# HIP4081A_v1_2.net
KiCad netlist of a schematic drawn in EAGLE
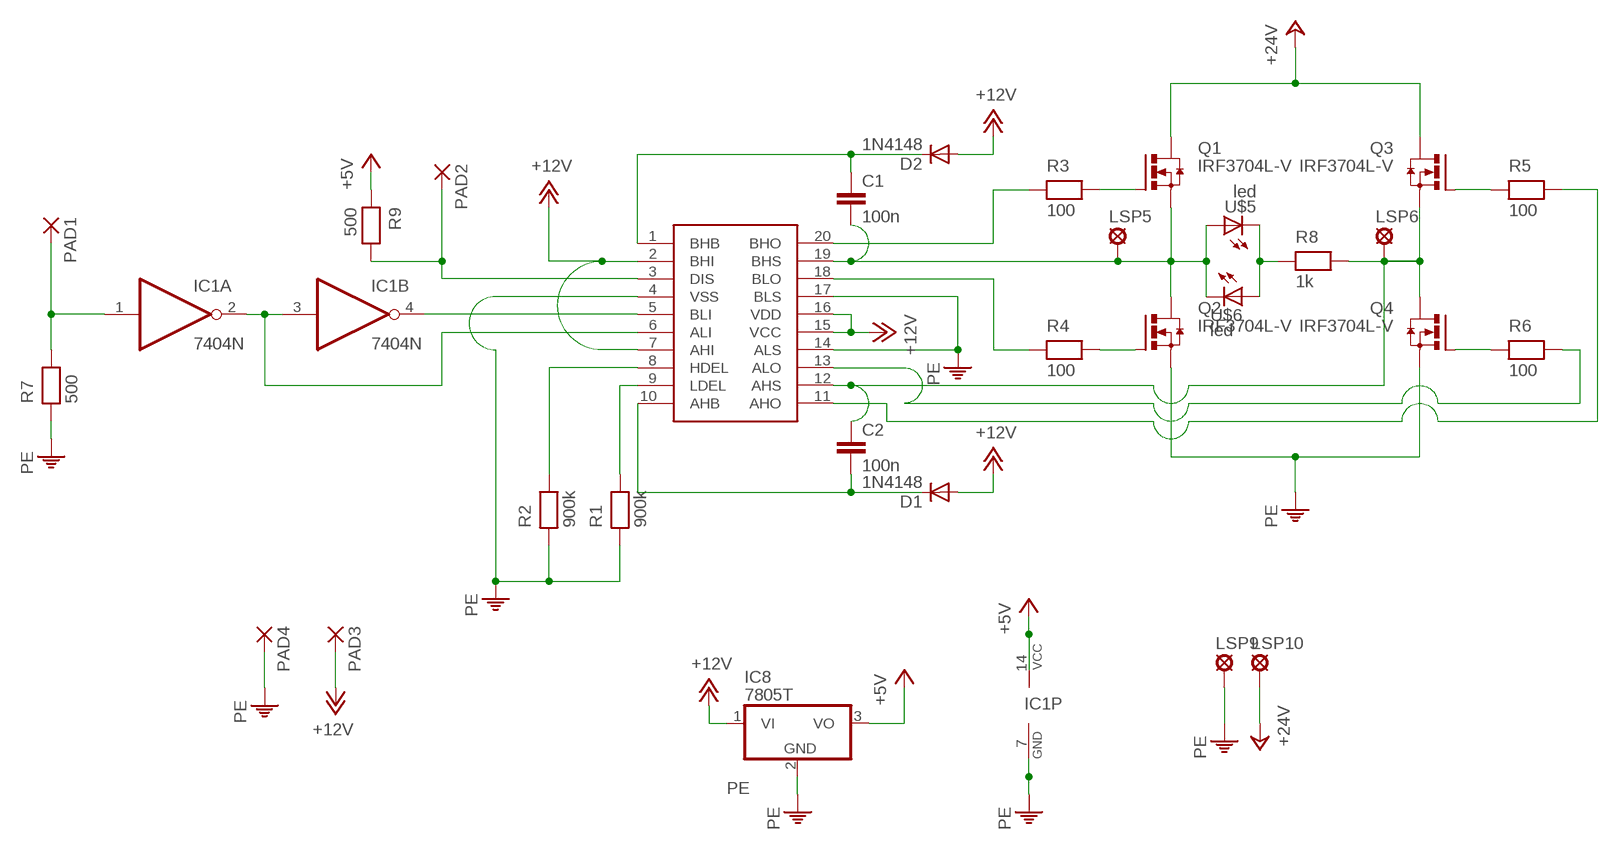
[diagram p0: schematic, sheet 1]

(export (version "E")
  (design (tool "Eeschema 10.0.6"))
  (components
    (comp (ref "C1")
      (value "100n")
      (footprint "eagle-import:C5B2.5")
      (libsource (lib "eagle-import") (part "C5/2.5"))
    )
    (comp (ref "C2")
      (value "100n")
      (footprint "eagle-import:C5B2.5")
      (libsource (lib "eagle-import") (part "C5/2.5"))
    )
    (comp (ref "D1")
      (value "1N4148")
      (footprint "eagle-import:DO35-10")
      (libsource (lib "eagle-import") (part "1N4148"))
    )
    (comp (ref "D2")
      (value "1N4148")
      (footprint "eagle-import:DO35-10")
      (libsource (lib "eagle-import") (part "1N4148"))
    )
    (comp (ref "IC1")
      (value "7404N")
      (footprint "eagle-import:DIL14")
      (libsource (lib "eagle-import") (part "7404N"))
    )
    (comp (ref "IC2")
      (value "HIP4081A")
      (footprint "eagle-import:DIL20")
      (libsource (lib "eagle-import") (part "HIP4081A"))
    )
    (comp (ref "IC8")
      (value "7805T")
      (footprint "eagle-import:TO220H")
      (libsource (lib "eagle-import") (part "78T05"))
    )
    (comp (ref "LSP5")
      (value "SE14")
      (footprint "eagle-import:SE14")
      (libsource (lib "eagle-import") (part "SE14"))
    )
    (comp (ref "LSP6")
      (value "SE14")
      (footprint "eagle-import:SE14")
      (libsource (lib "eagle-import") (part "SE14"))
    )
    (comp (ref "LSP9")
      (value "SE14")
      (footprint "eagle-import:SE14")
      (libsource (lib "eagle-import") (part "SE14"))
    )
    (comp (ref "LSP10")
      (value "SE14")
      (footprint "eagle-import:SE14")
      (libsource (lib "eagle-import") (part "SE14"))
    )
    (comp (ref "PAD1")
      (value "1,6/0,8")
      (footprint "eagle-import:1,6_0,8")
      (libsource (lib "eagle-import") (part "1,6/0,8"))
    )
    (comp (ref "PAD2")
      (value "1,6/0,8")
      (footprint "eagle-import:1,6_0,8")
      (libsource (lib "eagle-import") (part "1,6/0,8"))
    )
    (comp (ref "PAD3")
      (value "1,6/0,8")
      (footprint "eagle-import:1,6_0,8")
      (libsource (lib "eagle-import") (part "1,6/0,8"))
    )
    (comp (ref "PAD4")
      (value "1,6/0,8")
      (footprint "eagle-import:1,6_0,8")
      (libsource (lib "eagle-import") (part "1,6/0,8"))
    )
    (comp (ref "Q1")
      (value "IRF3704L-V")
      (footprint "eagle-import:TO262-V")
      (libsource (lib "eagle-import") (part "IRF3704L-V"))
    )
    (comp (ref "Q2")
      (value "IRF3704L-V")
      (footprint "eagle-import:TO262-V")
      (libsource (lib "eagle-import") (part "IRF3704L-V"))
    )
    (comp (ref "Q3")
      (value "IRF3704L-V")
      (footprint "eagle-import:TO262-V")
      (libsource (lib "eagle-import") (part "IRF3704L-V"))
    )
    (comp (ref "Q4")
      (value "IRF3704L-V")
      (footprint "eagle-import:TO262-V")
      (libsource (lib "eagle-import") (part "IRF3704L-V"))
    )
    (comp (ref "R1")
      (value "900k")
      (footprint "eagle-import:R-10")
      (libsource (lib "eagle-import") (part "RESEU-10"))
    )
    (comp (ref "R2")
      (value "900k")
      (footprint "eagle-import:R-10")
      (libsource (lib "eagle-import") (part "RESEU-10"))
    )
    (comp (ref "R3")
      (value "100")
      (footprint "eagle-import:R-10")
      (libsource (lib "eagle-import") (part "RESEU-10"))
    )
    (comp (ref "R4")
      (value "100")
      (footprint "eagle-import:R-10")
      (libsource (lib "eagle-import") (part "RESEU-10"))
    )
    (comp (ref "R5")
      (value "100")
      (footprint "eagle-import:R-10")
      (libsource (lib "eagle-import") (part "RESEU-10"))
    )
    (comp (ref "R6")
      (value "100")
      (footprint "eagle-import:R-10")
      (libsource (lib "eagle-import") (part "RESEU-10"))
    )
    (comp (ref "R7")
      (value "500")
      (footprint "eagle-import:R-10")
      (libsource (lib "eagle-import") (part "RESEU-10"))
    )
    (comp (ref "R8")
      (value "1k")
      (footprint "eagle-import:R-10")
      (libsource (lib "eagle-import") (part "RESEU-10"))
    )
    (comp (ref "R9")
      (value "500")
      (footprint "eagle-import:R-10")
      (libsource (lib "eagle-import") (part "RESEU-10"))
    )
    (comp (ref "U$5")
      (value "led")
      (footprint "eagle-import:LED3MM")
      (libsource (lib "eagle-import") (part "LED3MM"))
    )
    (comp (ref "U$6")
      (value "led")
      (footprint "eagle-import:LED3MM")
      (libsource (lib "eagle-import") (part "LED3MM"))
    )
  )
  (nets
    (net (code "1") (name "+5V") (class "Default")
      (node (ref "IC1") (pin "14") (pinfunction "VCC_14") (pintype "power_in"))
      (node (ref "IC8") (pin "3") (pinfunction "VO_3") (pintype "passive"))
      (node (ref "R9") (pin "1") (pinfunction "1_1") (pintype "passive"))
    )
    (net (code "2") (name "+12V") (class "Default")
      (node (ref "D1") (pin "A") (pinfunction "A_A") (pintype "passive"))
      (node (ref "D2") (pin "A") (pinfunction "A_A") (pintype "passive"))
      (node (ref "IC2") (pin "15") (pinfunction "VCC_15") (pintype "input"))
      (node (ref "IC2") (pin "16") (pinfunction "VDD_16") (pintype "input"))
      (node (ref "IC2") (pin "2") (pinfunction "BHI_2") (pintype "bidirectional"))
      (node (ref "IC2") (pin "7") (pinfunction "AHI_7") (pintype "bidirectional"))
      (node (ref "IC8") (pin "1") (pinfunction "VI_1") (pintype "input"))
      (node (ref "PAD3") (pin "1") (pinfunction "P_1") (pintype "passive"))
    )
    (net (code "3") (name "+24V") (class "Default")
      (node (ref "LSP10") (pin "MP") (pinfunction "MP_MP") (pintype "passive"))
      (node (ref "Q1") (pin "2") (pinfunction "D_2") (pintype "passive"))
      (node (ref "Q3") (pin "2") (pinfunction "D_2") (pintype "passive"))
    )
    (net (code "4") (name "Net-(IC1A-I)") (class "Default")
      (node (ref "IC1") (pin "1") (pinfunction "I_1") (pintype "input"))
      (node (ref "PAD1") (pin "1") (pinfunction "P_1") (pintype "passive"))
      (node (ref "R7") (pin "2") (pinfunction "2_2") (pintype "passive"))
    )
    (net (code "5") (name "Net-(IC1A-O)") (class "Default")
      (node (ref "IC1") (pin "2") (pinfunction "O_2") (pintype "output"))
      (node (ref "IC1") (pin "3") (pinfunction "I_3") (pintype "input"))
      (node (ref "IC2") (pin "6") (pinfunction "ALI_6") (pintype "bidirectional"))
    )
    (net (code "6") (name "Net-(IC1B-O)") (class "Default")
      (node (ref "IC1") (pin "4") (pinfunction "O_4") (pintype "output"))
      (node (ref "IC2") (pin "5") (pinfunction "BLI_5") (pintype "bidirectional"))
    )
    (net (code "7") (name "Net-(IC2-AHB)") (class "Default")
      (node (ref "C2") (pin "2") (pinfunction "2_2") (pintype "passive"))
      (node (ref "D1") (pin "C") (pinfunction "C_C") (pintype "passive"))
      (node (ref "IC2") (pin "10") (pinfunction "AHB_10") (pintype "bidirectional"))
    )
    (net (code "8") (name "Net-(IC2-AHO)") (class "Default")
      (node (ref "IC2") (pin "11") (pinfunction "AHO_11") (pintype "output"))
      (node (ref "R5") (pin "2") (pinfunction "2_2") (pintype "passive"))
    )
    (net (code "9") (name "Net-(IC2-AHS)") (class "Default")
      (node (ref "C2") (pin "1") (pinfunction "1_1") (pintype "passive"))
      (node (ref "IC2") (pin "12") (pinfunction "AHS_12") (pintype "input"))
      (node (ref "LSP6") (pin "MP") (pinfunction "MP_MP") (pintype "passive"))
      (node (ref "Q3") (pin "3") (pinfunction "S_3") (pintype "passive"))
      (node (ref "Q4") (pin "2") (pinfunction "D_2") (pintype "passive"))
      (node (ref "R8") (pin "2") (pinfunction "2_2") (pintype "passive"))
    )
    (net (code "10") (name "Net-(IC2-ALO)") (class "Default")
      (node (ref "IC2") (pin "13") (pinfunction "ALO_13") (pintype "output"))
      (node (ref "R6") (pin "2") (pinfunction "2_2") (pintype "passive"))
    )
    (net (code "11") (name "Net-(IC2-BHB)") (class "Default")
      (node (ref "C1") (pin "1") (pinfunction "1_1") (pintype "passive"))
      (node (ref "D2") (pin "C") (pinfunction "C_C") (pintype "passive"))
      (node (ref "IC2") (pin "1") (pinfunction "BHB_1") (pintype "bidirectional"))
    )
    (net (code "12") (name "Net-(IC2-BHO)") (class "Default")
      (node (ref "IC2") (pin "20") (pinfunction "BHO_20") (pintype "output"))
      (node (ref "R3") (pin "1") (pinfunction "1_1") (pintype "passive"))
    )
    (net (code "13") (name "Net-(IC2-BHS)") (class "Default")
      (node (ref "C1") (pin "2") (pinfunction "2_2") (pintype "passive"))
      (node (ref "IC2") (pin "19") (pinfunction "BHS_19") (pintype "input"))
      (node (ref "LSP5") (pin "MP") (pinfunction "MP_MP") (pintype "passive"))
      (node (ref "Q1") (pin "3") (pinfunction "S_3") (pintype "passive"))
      (node (ref "Q2") (pin "2") (pinfunction "D_2") (pintype "passive"))
      (node (ref "U$5") (pin "A") (pinfunction "A_A") (pintype "passive"))
      (node (ref "U$6") (pin "K") (pinfunction "C_K") (pintype "passive"))
    )
    (net (code "14") (name "Net-(IC2-BLO)") (class "Default")
      (node (ref "IC2") (pin "18") (pinfunction "BLO_18") (pintype "output"))
      (node (ref "R4") (pin "1") (pinfunction "1_1") (pintype "passive"))
    )
    (net (code "15") (name "Net-(IC2-DIS)") (class "Default")
      (node (ref "IC2") (pin "3") (pinfunction "DIS_3") (pintype "input"))
      (node (ref "PAD2") (pin "1") (pinfunction "P_1") (pintype "passive"))
      (node (ref "R9") (pin "2") (pinfunction "2_2") (pintype "passive"))
    )
    (net (code "16") (name "Net-(IC2-HDEL)") (class "Default")
      (node (ref "IC2") (pin "8") (pinfunction "HDEL_8") (pintype "bidirectional"))
      (node (ref "R2") (pin "2") (pinfunction "2_2") (pintype "passive"))
    )
    (net (code "17") (name "Net-(IC2-LDEL)") (class "Default")
      (node (ref "IC2") (pin "9") (pinfunction "LDEL_9") (pintype "bidirectional"))
      (node (ref "R1") (pin "2") (pinfunction "2_2") (pintype "passive"))
    )
    (net (code "18") (name "Net-(Q1-G)") (class "Default")
      (node (ref "Q1") (pin "1") (pinfunction "G_1") (pintype "passive"))
      (node (ref "R3") (pin "2") (pinfunction "2_2") (pintype "passive"))
    )
    (net (code "19") (name "Net-(Q2-G)") (class "Default")
      (node (ref "Q2") (pin "1") (pinfunction "G_1") (pintype "passive"))
      (node (ref "R4") (pin "2") (pinfunction "2_2") (pintype "passive"))
    )
    (net (code "20") (name "Net-(Q3-G)") (class "Default")
      (node (ref "Q3") (pin "1") (pinfunction "G_1") (pintype "passive"))
      (node (ref "R5") (pin "1") (pinfunction "1_1") (pintype "passive"))
    )
    (net (code "21") (name "Net-(Q4-G)") (class "Default")
      (node (ref "Q4") (pin "1") (pinfunction "G_1") (pintype "passive"))
      (node (ref "R6") (pin "1") (pinfunction "1_1") (pintype "passive"))
    )
    (net (code "22") (name "Net-(U$5-C)") (class "Default")
      (node (ref "R8") (pin "1") (pinfunction "1_1") (pintype "passive"))
      (node (ref "U$5") (pin "K") (pinfunction "C_K") (pintype "passive"))
      (node (ref "U$6") (pin "A") (pinfunction "A_A") (pintype "passive"))
    )
    (net (code "23") (name "PE") (class "Default")
      (node (ref "IC1") (pin "7") (pinfunction "GND_7") (pintype "power_in"))
      (node (ref "IC2") (pin "14") (pinfunction "ALS_14") (pintype "input"))
      (node (ref "IC2") (pin "17") (pinfunction "BLS_17") (pintype "input"))
      (node (ref "IC2") (pin "4") (pinfunction "VSS_4") (pintype "input"))
      (node (ref "IC8") (pin "2") (pinfunction "GND_2") (pintype "passive"))
      (node (ref "LSP9") (pin "MP") (pinfunction "MP_MP") (pintype "passive"))
      (node (ref "PAD4") (pin "1") (pinfunction "P_1") (pintype "passive"))
      (node (ref "Q2") (pin "3") (pinfunction "S_3") (pintype "passive"))
      (node (ref "Q4") (pin "3") (pinfunction "S_3") (pintype "passive"))
      (node (ref "R1") (pin "1") (pinfunction "1_1") (pintype "passive"))
      (node (ref "R2") (pin "1") (pinfunction "1_1") (pintype "passive"))
      (node (ref "R7") (pin "1") (pinfunction "1_1") (pintype "passive"))
    )
  )
)
